# JadePlus_v0_3_1_schematics_PG2_PMS.net
KiCad netlist of a schematic drawn in Altium Designer
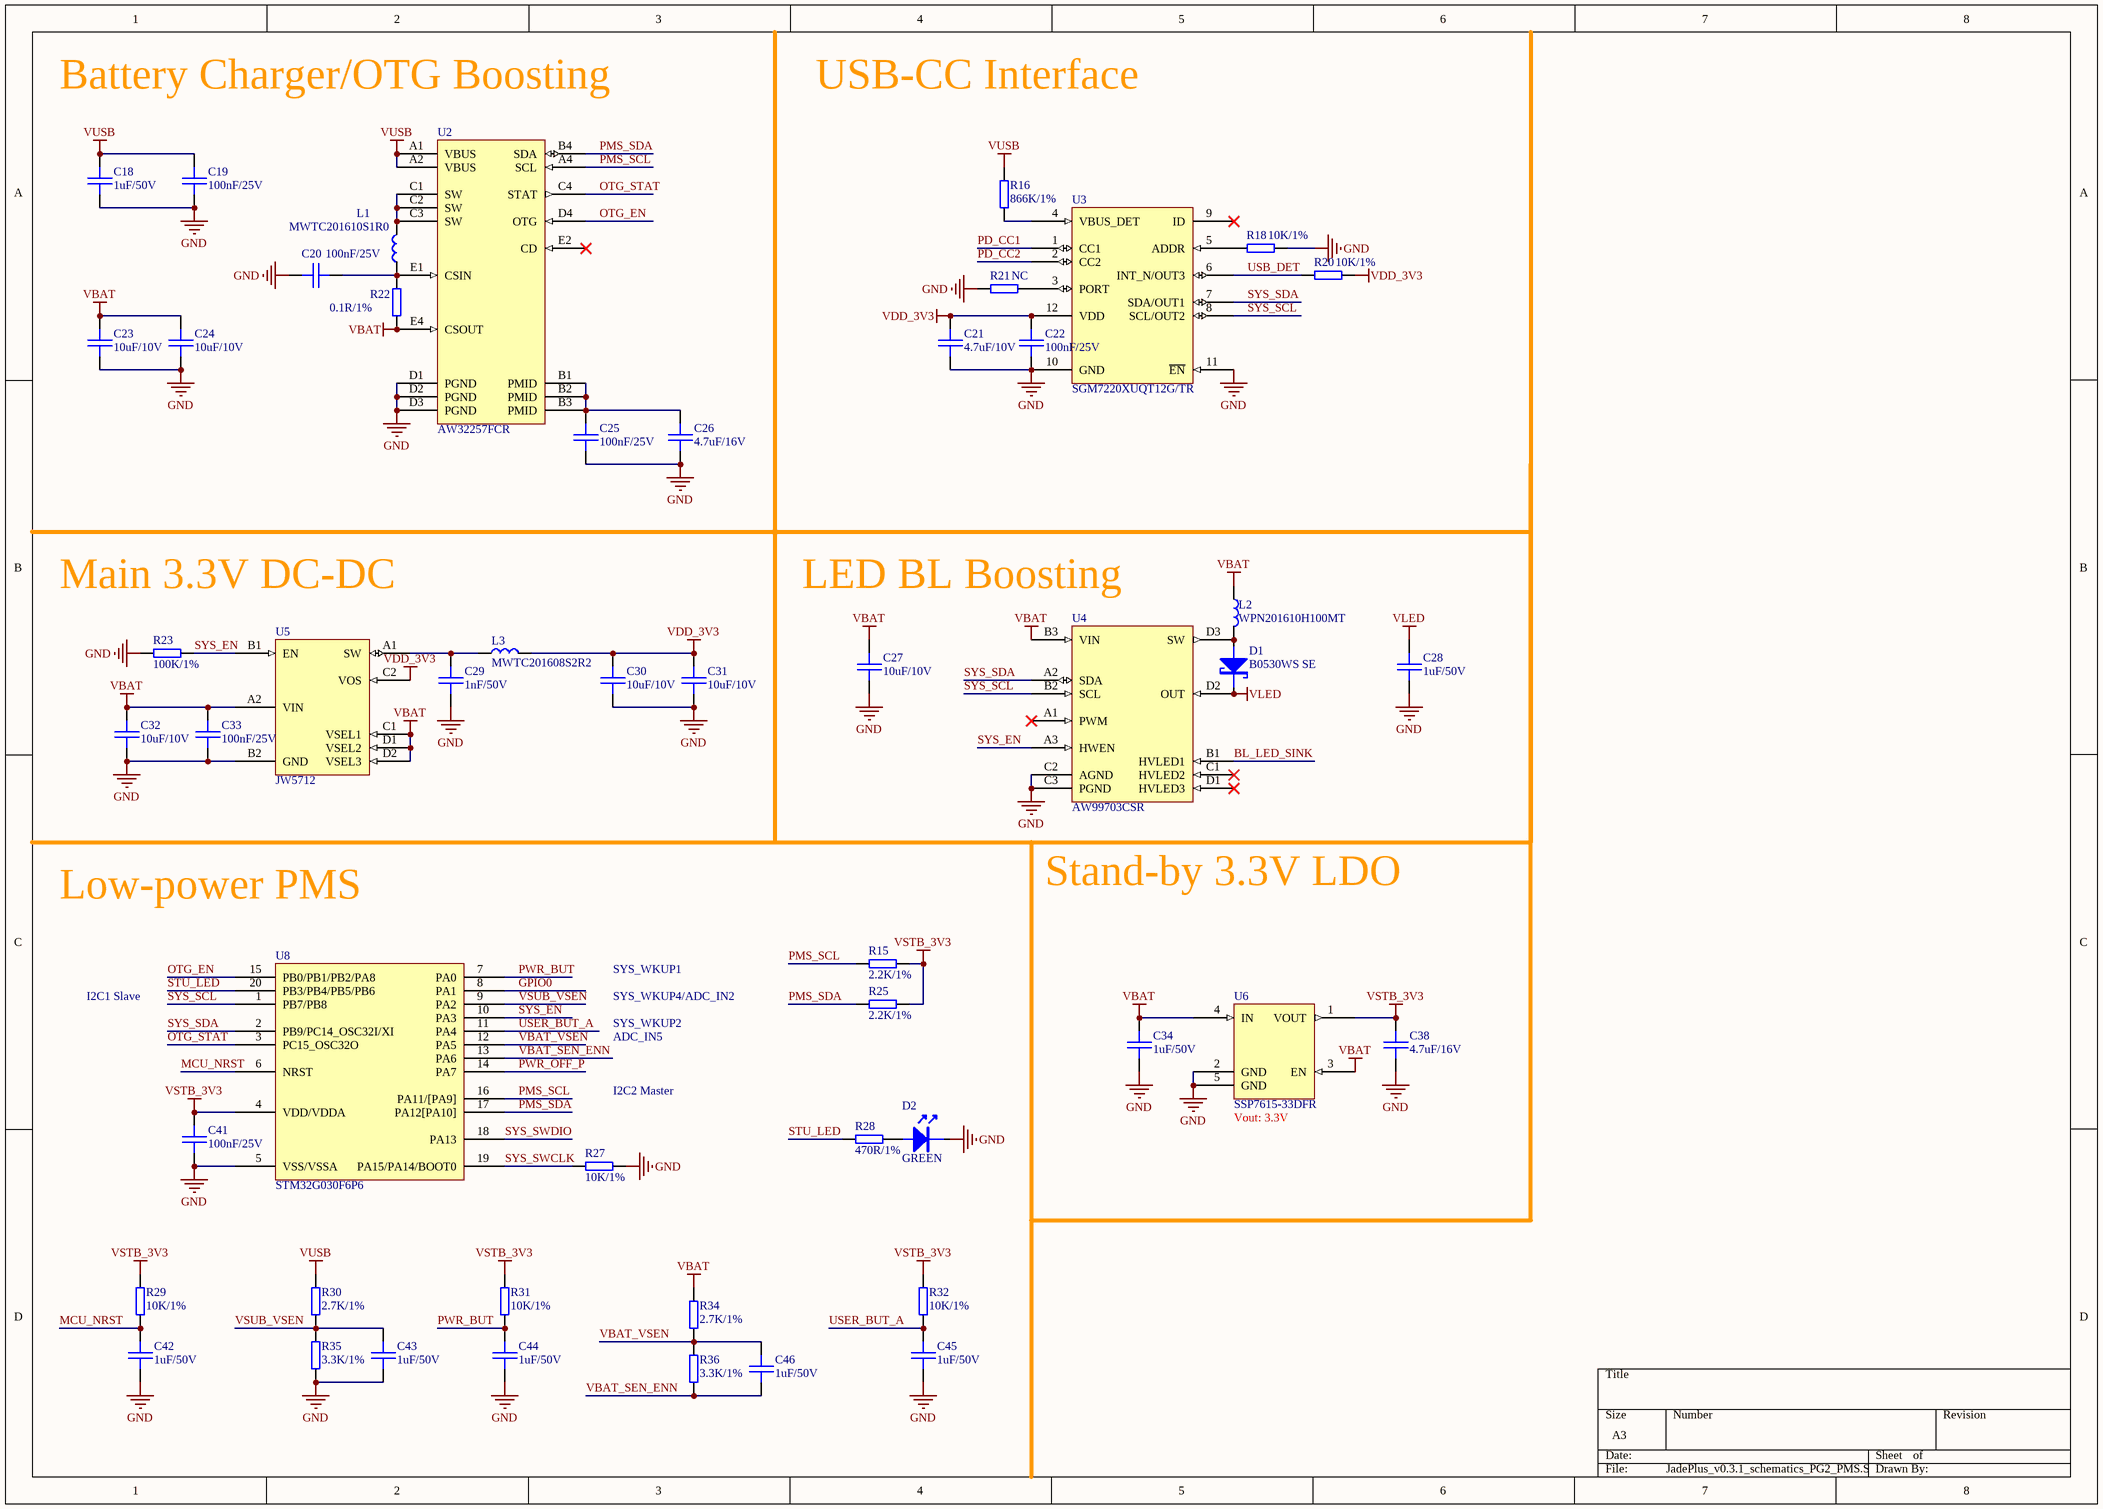
[diagram p0: JadePlus_v0.3.1_schematics_PG2_PMS.SchDoc]

(export (version "E")
  (design (tool "Eeschema 10.0.6"))
  (components
    (comp (ref "C18")
      (value "1uF/50V")
      (footprint "HD-Components:C0402-L-HD")
      (description "Surface mount capacitor 0402")
      (libsource (lib "Vowstar_Basic_Device") (part "SMT_C_0402"))
    )
    (comp (ref "C19")
      (value "100nF/25V")
      (footprint "C0201-HD")
      (description "Surface mount capacitor 0402")
      (libsource (lib "Vowstar_Basic_Device") (part "SMT_C_0402"))
    )
    (comp (ref "C20")
      (value "100nF/25V")
      (footprint "HD-Components:C0402-HD")
      (description "Surface mount capacitor 0402")
      (libsource (lib "Vowstar_Basic_Device") (part "SMT_C_0402"))
    )
    (comp (ref "C21")
      (value "4.7uF/10V")
      (footprint "C0402-L-HD")
      (description "Surface mount capacitor 0402")
      (libsource (lib "Vowstar_Basic_Device") (part "SMT_C_0402"))
    )
    (comp (ref "C22")
      (value "100nF/25V")
      (footprint "C0201-HD")
      (description "Surface mount capacitor 0402")
      (libsource (lib "Vowstar_Basic_Device") (part "SMT_C_0402"))
    )
    (comp (ref "C23")
      (value "10uF/10V")
      (footprint "HD-Components:C0402-L-HD")
      (description "Surface mount capacitor 0402")
      (libsource (lib "Vowstar_Basic_Device") (part "SMT_C_0402"))
    )
    (comp (ref "C24")
      (value "10uF/10V")
      (footprint "HD-Components:C0402-L-HD")
      (description "Surface mount capacitor 0402")
      (libsource (lib "Vowstar_Basic_Device") (part "SMT_C_0402"))
    )
    (comp (ref "C25")
      (value "100nF/25V")
      (footprint "C0201-HD")
      (description "Surface mount capacitor 0402")
      (libsource (lib "Vowstar_Basic_Device") (part "SMT_C_0402"))
    )
    (comp (ref "C26")
      (value "4.7uF/16V")
      (footprint "HD-Components:C0402-L-HD")
      (description "Surface mount capacitor 0402")
      (libsource (lib "Vowstar_Basic_Device") (part "SMT_C_0402"))
    )
    (comp (ref "C27")
      (value "10uF/10V")
      (footprint "HD-Components:C0402-L-HD")
      (description "Surface mount capacitor 0402")
      (libsource (lib "Vowstar_Basic_Device") (part "SMT_C_0402"))
    )
    (comp (ref "C28")
      (value "1uF/50V")
      (footprint "HD-Components:C0402-L-HD")
      (description "Surface mount capacitor 0402")
      (libsource (lib "Vowstar_Basic_Device") (part "SMT_C_0402"))
    )
    (comp (ref "C29")
      (value "1nF/50V")
      (footprint "C0201-HD")
      (description "Surface mount capacitor 0402")
      (libsource (lib "Vowstar_Basic_Device") (part "SMT_C_0402"))
    )
    (comp (ref "C30")
      (value "10uF/10V")
      (footprint "HD-Components:C0402-L-HD")
      (description "Surface mount capacitor 0402")
      (libsource (lib "Vowstar_Basic_Device") (part "SMT_C_0402"))
    )
    (comp (ref "C31")
      (value "10uF/10V")
      (footprint "HD-Components:C0402-L-HD")
      (description "Surface mount capacitor 0402")
      (libsource (lib "Vowstar_Basic_Device") (part "SMT_C_0402"))
    )
    (comp (ref "C32")
      (value "10uF/10V")
      (footprint "HD-Components:C0402-L-HD")
      (description "Surface mount capacitor 0402")
      (libsource (lib "Vowstar_Basic_Device") (part "SMT_C_0402"))
    )
    (comp (ref "C33")
      (value "100nF/25V")
      (footprint "C0201-HD")
      (description "Surface mount capacitor 0402")
      (libsource (lib "Vowstar_Basic_Device") (part "SMT_C_0402"))
    )
    (comp (ref "C34")
      (value "1uF/50V")
      (footprint "HD-Components:C0402-L-HD")
      (description "Surface mount capacitor 0402")
      (libsource (lib "Vowstar_Basic_Device") (part "SMT_C_0402"))
    )
    (comp (ref "C38")
      (value "4.7uF/16V")
      (footprint "HD-Components:C0402-L-HD")
      (description "Surface mount capacitor 0402")
      (libsource (lib "Vowstar_Basic_Device") (part "SMT_C_0402"))
    )
    (comp (ref "C41")
      (value "100nF/25V")
      (footprint "C0201-HD")
      (description "Surface mount capacitor 0402")
      (libsource (lib "Vowstar_Basic_Device") (part "SMT_C_0402"))
    )
    (comp (ref "C42")
      (value "1uF/50V")
      (footprint "HD-Components:C0402-L-HD")
      (description "Surface mount capacitor 0402")
      (libsource (lib "Vowstar_Basic_Device") (part "SMT_C_0402"))
    )
    (comp (ref "C43")
      (value "1uF/50V")
      (footprint "HD-Components:C0402-L-HD")
      (description "Surface mount capacitor 0402")
      (libsource (lib "Vowstar_Basic_Device") (part "SMT_C_0402"))
    )
    (comp (ref "C44")
      (value "1uF/50V")
      (footprint "HD-Components:C0402-L-HD")
      (description "Surface mount capacitor 0402")
      (libsource (lib "Vowstar_Basic_Device") (part "SMT_C_0402"))
    )
    (comp (ref "C45")
      (value "1uF/50V")
      (footprint "HD-Components:C0402-L-HD")
      (description "Surface mount capacitor 0402")
      (libsource (lib "Vowstar_Basic_Device") (part "SMT_C_0402"))
    )
    (comp (ref "C46")
      (value "1uF/50V")
      (footprint "HD-Components:C0402-L-HD")
      (description "Surface mount capacitor 0402")
      (libsource (lib "Vowstar_Basic_Device") (part "SMT_C_0402"))
    )
    (comp (ref "D1")
      (value "B0530WS SE")
      (footprint "SMT_DIODE_SOD_323")
      (description "Surface mount schottky diode SOD-323(0805) Package\r\nC22626")
      (libsource (lib "Vowstar_Basic_Device") (part "SMT_DIODE_SCHOTTKY_SOD_323"))
    )
    (comp (ref "D2")
      (value "GREEN")
      (footprint "SMT_LED_0603")
      (description "Surface mount LED 0603")
      (libsource (lib "Vowstar_Basic_Device") (part "SMT_LED_0603"))
    )
    (comp (ref "L1")
      (value "MWTC201610S1R0")
      (footprint "MWTC201610-HD")
      (description "Surface mount inductor 0805")
      (libsource (lib "") (part "SMT_L_0805_1"))
    )
    (comp (ref "L2")
      (value "WPN201610H100MT")
      (footprint "MWTC201610-HD")
      (description "Surface mount inductor 0805")
      (libsource (lib "Vowstar_Basic_Device") (part "SMT_L_0805"))
    )
    (comp (ref "L3")
      (value "MWTC201608S2R2")
      (footprint "MWTC201610-HD")
      (description "Surface mount inductor 0805")
      (libsource (lib "") (part "SMT_L_0805_1"))
    )
    (comp (ref "R15")
      (value "2.2K/1%")
      (footprint "R0402-HD")
      (description "Surface mount resistor 0402")
      (libsource (lib "Vowstar_Basic_Device") (part "SMT_R_0402"))
    )
    (comp (ref "R16")
      (value "866K/1%")
      (footprint "R0402-HD")
      (description "Surface mount resistor 0402")
      (libsource (lib "Vowstar_Basic_Device") (part "SMT_R_0402"))
    )
    (comp (ref "R18")
      (value "10K/1%")
      (footprint "R0402-HD")
      (description "Surface mount resistor 0402")
      (libsource (lib "Vowstar_Basic_Device") (part "SMT_R_0402"))
    )
    (comp (ref "R20")
      (value "10K/1%")
      (footprint "R0402-HD")
      (description "Surface mount resistor 0402")
      (libsource (lib "Vowstar_Basic_Device") (part "SMT_R_0402"))
    )
    (comp (ref "R21")
      (value "NC")
      (footprint "R0402-HD")
      (description "Surface mount resistor 0402")
      (libsource (lib "Vowstar_Basic_Device") (part "SMT_R_0402"))
    )
    (comp (ref "R22")
      (value "0.1R/1%")
      (footprint "R0603-HD")
      (description "Surface mount resistor 0603")
      (libsource (lib "Vowstar_Basic_Device") (part "SMT_R_0603"))
    )
    (comp (ref "R23")
      (value "100K/1%")
      (footprint "R0402-HD")
      (description "Surface mount resistor 0402")
      (libsource (lib "Vowstar_Basic_Device") (part "SMT_R_0402"))
    )
    (comp (ref "R25")
      (value "2.2K/1%")
      (footprint "R0402-HD")
      (description "Surface mount resistor 0402")
      (libsource (lib "Vowstar_Basic_Device") (part "SMT_R_0402"))
    )
    (comp (ref "R27")
      (value "10K/1%")
      (footprint "R0402-HD")
      (description "Surface mount resistor 0402")
      (libsource (lib "Vowstar_Basic_Device") (part "SMT_R_0402"))
    )
    (comp (ref "R28")
      (value "470R/1%")
      (footprint "R0402-HD")
      (description "Surface mount resistor 0402")
      (libsource (lib "Vowstar_Basic_Device") (part "SMT_R_0402"))
    )
    (comp (ref "R29")
      (value "10K/1%")
      (footprint "R0402-HD")
      (description "Surface mount resistor 0402")
      (libsource (lib "Vowstar_Basic_Device") (part "SMT_R_0402"))
    )
    (comp (ref "R30")
      (value "2.7K/1%")
      (footprint "R0402-HD")
      (description "Surface mount resistor 0402")
      (libsource (lib "Vowstar_Basic_Device") (part "SMT_R_0402"))
    )
    (comp (ref "R31")
      (value "10K/1%")
      (footprint "R0402-HD")
      (description "Surface mount resistor 0402")
      (libsource (lib "Vowstar_Basic_Device") (part "SMT_R_0402"))
    )
    (comp (ref "R32")
      (value "10K/1%")
      (footprint "R0402-HD")
      (description "Surface mount resistor 0402")
      (libsource (lib "Vowstar_Basic_Device") (part "SMT_R_0402"))
    )
    (comp (ref "R34")
      (value "2.7K/1%")
      (footprint "R0402-HD")
      (description "Surface mount resistor 0402")
      (libsource (lib "Vowstar_Basic_Device") (part "SMT_R_0402"))
    )
    (comp (ref "R35")
      (value "3.3K/1%")
      (footprint "R0402-HD")
      (description "Surface mount resistor 0402")
      (libsource (lib "Vowstar_Basic_Device") (part "SMT_R_0402"))
    )
    (comp (ref "R36")
      (value "3.3K/1%")
      (footprint "R0402-HD")
      (description "Surface mount resistor 0402")
      (libsource (lib "Vowstar_Basic_Device") (part "SMT_R_0402"))
    )
    (comp (ref "U2")
      (value "AW32257FCR")
      (footprint "BGA20C40P4X5_200X200X60")
      (libsource (lib "GENERAL-IC") (part "AW32257"))
    )
    (comp (ref "U3")
      (value "SGM7220XUQT12G/TR")
      (footprint "QFN40P160X160X60-12L")
      (description "SGM7220XUQT12G/TR\r\nTUSB320\r\nHUSB320_BA000-QN12R")
      (libsource (lib "GENERAL-IC") (part "SGM7220"))
    )
    (comp (ref "U4")
      (value "AW99703CSR")
      (footprint "BGA12C40P3X4_124X164X64")
      (libsource (lib "GENERAL-IC") (part "AW99703"))
    )
    (comp (ref "U5")
      (value "JW5712")
      (footprint "BGA8C40P2X4_86X156X60")
      (libsource (lib "GENERAL-IC") (part "JW5712"))
    )
    (comp (ref "U6")
      (value "SSP7615-33DFR")
      (footprint "X2SON4")
      (description "300mA HIGH PSRR LOW NOISE LDO WITH ENABLE")
      (libsource (lib "GENERAL-IC") (part "AP7343"))
    )
    (comp (ref "U8")
      (value "STM32G030F6P6")
      (footprint "TSOP-20-HD")
      (libsource (lib "GENERAL-IC") (part "STM32G030F6P6"))
    )
  )
  (nets
    (net (code "1") (name "/BL_LED_SINK") (class "Default")
      (node (ref "U4") (pin "B1") (pinfunction "HVLED1_B1") (pintype "input"))
    )
    (net (code "2") (name "/GPIO0") (class "Default")
      (node (ref "U8") (pin "8") (pinfunction "PA1_8") (pintype "passive"))
    )
    (net (code "3") (name "/MCU_NRST") (class "Default")
      (node (ref "C42") (pin "2") (pinfunction "2_2") (pintype "passive"))
      (node (ref "R29") (pin "2") (pinfunction "2_2") (pintype "passive"))
      (node (ref "U8") (pin "6") (pinfunction "NRST_6") (pintype "passive"))
    )
    (net (code "4") (name "/OTG_EN") (class "Default")
      (node (ref "U2") (pin "D4") (pinfunction "OTG_D4") (pintype "input"))
      (node (ref "U8") (pin "15") (pinfunction "PB0/PB1/PB2/PA8_15") (pintype "passive"))
    )
    (net (code "5") (name "/OTG_STAT") (class "Default")
      (node (ref "U2") (pin "C4") (pinfunction "STAT_C4") (pintype "output"))
      (node (ref "U8") (pin "3") (pinfunction "PC15_OSC32O_3") (pintype "passive"))
    )
    (net (code "6") (name "/PD_CC1") (class "Default")
      (node (ref "U3") (pin "1") (pinfunction "CC1_1") (pintype "bidirectional"))
    )
    (net (code "7") (name "/PD_CC2") (class "Default")
      (node (ref "U3") (pin "2") (pinfunction "CC2_2") (pintype "bidirectional"))
    )
    (net (code "8") (name "/PMS_SCL") (class "Default")
      (node (ref "R15") (pin "1") (pinfunction "1_1") (pintype "passive"))
      (node (ref "U2") (pin "A4") (pinfunction "SCL_A4") (pintype "input"))
      (node (ref "U8") (pin "16") (pinfunction "PA11/[PA9]_16") (pintype "passive"))
    )
    (net (code "9") (name "/PMS_SDA") (class "Default")
      (node (ref "R25") (pin "1") (pinfunction "1_1") (pintype "passive"))
      (node (ref "U2") (pin "B4") (pinfunction "SDA_B4") (pintype "bidirectional"))
      (node (ref "U8") (pin "17") (pinfunction "PA12[PA10]_17") (pintype "passive"))
    )
    (net (code "10") (name "/PWR_BUT") (class "Default")
      (node (ref "C44") (pin "2") (pinfunction "2_2") (pintype "passive"))
      (node (ref "R31") (pin "2") (pinfunction "2_2") (pintype "passive"))
      (node (ref "U8") (pin "7") (pinfunction "PA0_7") (pintype "passive"))
    )
    (net (code "11") (name "/PWR_OFF_P") (class "Default")
      (node (ref "U8") (pin "14") (pinfunction "PA7_14") (pintype "passive"))
    )
    (net (code "12") (name "/STU_LED") (class "Default")
      (node (ref "R28") (pin "2") (pinfunction "2_2") (pintype "passive"))
      (node (ref "U8") (pin "20") (pinfunction "PB3/PB4/PB5/PB6_20") (pintype "passive"))
    )
    (net (code "13") (name "/SYS_EN") (class "Default")
      (node (ref "R23") (pin "2") (pinfunction "2_2") (pintype "passive"))
      (node (ref "U4") (pin "A3") (pinfunction "HWEN_A3") (pintype "input"))
      (node (ref "U5") (pin "B1") (pinfunction "EN_B1") (pintype "input"))
      (node (ref "U8") (pin "10") (pinfunction "PA3_10") (pintype "passive"))
    )
    (net (code "14") (name "/SYS_SCL") (class "Default")
      (node (ref "U3") (pin "8") (pinfunction "SCL/OUT2_8") (pintype "bidirectional"))
      (node (ref "U4") (pin "B2") (pinfunction "SCL_B2") (pintype "input"))
      (node (ref "U8") (pin "1") (pinfunction "PB7/PB8_1") (pintype "passive"))
    )
    (net (code "15") (name "/SYS_SDA") (class "Default")
      (node (ref "U3") (pin "7") (pinfunction "SDA/OUT1_7") (pintype "bidirectional"))
      (node (ref "U4") (pin "A2") (pinfunction "SDA_A2") (pintype "bidirectional"))
      (node (ref "U8") (pin "2") (pinfunction "PB9/PC14_OSC32I/XI_2") (pintype "passive"))
    )
    (net (code "16") (name "/SYS_SWCLK") (class "Default")
      (node (ref "R27") (pin "2") (pinfunction "2_2") (pintype "passive"))
      (node (ref "U8") (pin "19") (pinfunction "PA15/PA14/BOOT0_19") (pintype "passive"))
    )
    (net (code "17") (name "/SYS_SWDIO") (class "Default")
      (node (ref "U8") (pin "18") (pinfunction "PA13_18") (pintype "passive"))
    )
    (net (code "18") (name "/USB_DET") (class "Default")
      (node (ref "R20") (pin "1") (pinfunction "1_1") (pintype "passive"))
      (node (ref "U3") (pin "6") (pinfunction "INT_N/OUT3_6") (pintype "bidirectional"))
    )
    (net (code "19") (name "/USER_BUT_A") (class "Default")
      (node (ref "C45") (pin "2") (pinfunction "2_2") (pintype "passive"))
      (node (ref "R32") (pin "2") (pinfunction "2_2") (pintype "passive"))
      (node (ref "U8") (pin "11") (pinfunction "PA4_11") (pintype "passive"))
    )
    (net (code "20") (name "/VBAT_SEN_ENN") (class "Default")
      (node (ref "C46") (pin "1") (pinfunction "1_1") (pintype "passive"))
      (node (ref "R36") (pin "2") (pinfunction "2_2") (pintype "passive"))
      (node (ref "U8") (pin "13") (pinfunction "PA6_13") (pintype "passive"))
    )
    (net (code "21") (name "/VBAT_VSEN") (class "Default")
      (node (ref "C46") (pin "2") (pinfunction "2_2") (pintype "passive"))
      (node (ref "R34") (pin "2") (pinfunction "2_2") (pintype "passive"))
      (node (ref "R36") (pin "1") (pinfunction "1_1") (pintype "passive"))
      (node (ref "U8") (pin "12") (pinfunction "PA5_12") (pintype "passive"))
    )
    (net (code "22") (name "/VSUB_VSEN") (class "Default")
      (node (ref "C43") (pin "2") (pinfunction "2_2") (pintype "passive"))
      (node (ref "R30") (pin "2") (pinfunction "2_2") (pintype "passive"))
      (node (ref "R35") (pin "1") (pinfunction "1_1") (pintype "passive"))
      (node (ref "U8") (pin "9") (pinfunction "PA2_9") (pintype "passive"))
    )
    (net (code "23") (name "GND") (class "Default")
      (node (ref "C18") (pin "1") (pinfunction "1_1") (pintype "passive"))
      (node (ref "C19") (pin "1") (pinfunction "1_1") (pintype "passive"))
      (node (ref "C20") (pin "2") (pinfunction "2_2") (pintype "passive"))
      (node (ref "C21") (pin "1") (pinfunction "1_1") (pintype "passive"))
      (node (ref "C22") (pin "1") (pinfunction "1_1") (pintype "passive"))
      (node (ref "C23") (pin "1") (pinfunction "1_1") (pintype "passive"))
      (node (ref "C24") (pin "1") (pinfunction "1_1") (pintype "passive"))
      (node (ref "C25") (pin "1") (pinfunction "1_1") (pintype "passive"))
      (node (ref "C26") (pin "1") (pinfunction "1_1") (pintype "passive"))
      (node (ref "C27") (pin "1") (pinfunction "1_1") (pintype "passive"))
      (node (ref "C28") (pin "1") (pinfunction "1_1") (pintype "passive"))
      (node (ref "C29") (pin "1") (pinfunction "1_1") (pintype "passive"))
      (node (ref "C30") (pin "1") (pinfunction "1_1") (pintype "passive"))
      (node (ref "C31") (pin "1") (pinfunction "1_1") (pintype "passive"))
      (node (ref "C32") (pin "1") (pinfunction "1_1") (pintype "passive"))
      (node (ref "C33") (pin "1") (pinfunction "1_1") (pintype "passive"))
      (node (ref "C34") (pin "1") (pinfunction "1_1") (pintype "passive"))
      (node (ref "C38") (pin "1") (pinfunction "1_1") (pintype "passive"))
      (node (ref "C41") (pin "1") (pinfunction "1_1") (pintype "passive"))
      (node (ref "C42") (pin "1") (pinfunction "1_1") (pintype "passive"))
      (node (ref "C43") (pin "1") (pinfunction "1_1") (pintype "passive"))
      (node (ref "C44") (pin "1") (pinfunction "1_1") (pintype "passive"))
      (node (ref "C45") (pin "1") (pinfunction "1_1") (pintype "passive"))
      (node (ref "D2") (pin "2") (pinfunction "K_2") (pintype "passive"))
      (node (ref "R18") (pin "2") (pinfunction "2_2") (pintype "passive"))
      (node (ref "R21") (pin "1") (pinfunction "1_1") (pintype "passive"))
      (node (ref "R23") (pin "1") (pinfunction "1_1") (pintype "passive"))
      (node (ref "R27") (pin "1") (pinfunction "1_1") (pintype "passive"))
      (node (ref "R35") (pin "2") (pinfunction "2_2") (pintype "passive"))
      (node (ref "U2") (pin "D1") (pinfunction "PGND_D1") (pintype "power_in"))
      (node (ref "U2") (pin "D2") (pinfunction "PGND_D2") (pintype "power_in"))
      (node (ref "U2") (pin "D3") (pinfunction "PGND_D3") (pintype "power_in"))
      (node (ref "U3") (pin "10") (pinfunction "GND_10") (pintype "power_in"))
      (node (ref "U3") (pin "11") (pinfunction "~{EN}_11") (pintype "input"))
      (node (ref "U4") (pin "C2") (pinfunction "AGND_C2") (pintype "power_in"))
      (node (ref "U4") (pin "C3") (pinfunction "PGND_C3") (pintype "power_in"))
      (node (ref "U5") (pin "B2") (pinfunction "GND_B2") (pintype "power_in"))
      (node (ref "U6") (pin "2") (pinfunction "GND_2") (pintype "power_in"))
      (node (ref "U6") (pin "5") (pinfunction "GND_5") (pintype "power_in"))
      (node (ref "U8") (pin "5") (pinfunction "VSS/VSSA_5") (pintype "passive"))
    )
    (net (code "24") (name "Net-(C25-Pad2)") (class "Default")
      (node (ref "C25") (pin "2") (pinfunction "2_2") (pintype "passive"))
      (node (ref "C26") (pin "2") (pinfunction "2_2") (pintype "passive"))
      (node (ref "U2") (pin "B1") (pinfunction "PMID_B1") (pintype "power_in"))
      (node (ref "U2") (pin "B2") (pinfunction "PMID_B2") (pintype "power_in"))
      (node (ref "U2") (pin "B3") (pinfunction "PMID_B3") (pintype "power_in"))
    )
    (net (code "25") (name "Net-(D1-A)") (class "Default")
      (node (ref "D1") (pin "1") (pinfunction "A_1") (pintype "passive"))
      (node (ref "L2") (pin "2") (pinfunction "2_2") (pintype "passive"))
      (node (ref "U4") (pin "D3") (pinfunction "SW_D3") (pintype "output"))
    )
    (net (code "26") (name "Net-(D2-A)") (class "Default")
      (node (ref "D2") (pin "1") (pinfunction "A_1") (pintype "passive"))
      (node (ref "R28") (pin "1") (pinfunction "1_1") (pintype "passive"))
    )
    (net (code "27") (name "Net-(L1-Pad1)") (class "Default")
      (node (ref "L1") (pin "1") (pinfunction "1_1") (pintype "passive"))
      (node (ref "U2") (pin "C1") (pinfunction "SW_C1") (pintype "power_in"))
      (node (ref "U2") (pin "C2") (pinfunction "SW_C2") (pintype "power_in"))
      (node (ref "U2") (pin "C3") (pinfunction "SW_C3") (pintype "power_in"))
    )
    (net (code "28") (name "Net-(U2-CSIN)") (class "Default")
      (node (ref "C20") (pin "1") (pinfunction "1_1") (pintype "passive"))
      (node (ref "L1") (pin "2") (pinfunction "2_2") (pintype "passive"))
      (node (ref "R22") (pin "2") (pinfunction "2_2") (pintype "passive"))
      (node (ref "U2") (pin "E1") (pinfunction "CSIN_E1") (pintype "input"))
    )
    (net (code "29") (name "Net-(U3-ADDR)") (class "Default")
      (node (ref "R18") (pin "1") (pinfunction "1_1") (pintype "passive"))
      (node (ref "U3") (pin "5") (pinfunction "ADDR_5") (pintype "input"))
    )
    (net (code "30") (name "Net-(U3-PORT)") (class "Default")
      (node (ref "R21") (pin "2") (pinfunction "2_2") (pintype "passive"))
      (node (ref "U3") (pin "3") (pinfunction "PORT_3") (pintype "bidirectional"))
    )
    (net (code "31") (name "Net-(U3-VBUS_DET)") (class "Default")
      (node (ref "R16") (pin "2") (pinfunction "2_2") (pintype "passive"))
      (node (ref "U3") (pin "4") (pinfunction "VBUS_DET_4") (pintype "input"))
    )
    (net (code "32") (name "Net-(U5-SW)") (class "Default")
      (node (ref "C29") (pin "2") (pinfunction "2_2") (pintype "passive"))
      (node (ref "L3") (pin "2") (pinfunction "2_2") (pintype "passive"))
      (node (ref "U5") (pin "A1") (pinfunction "SW_A1") (pintype "bidirectional"))
    )
    (net (code "33") (name "VBAT") (class "Default")
      (node (ref "C23") (pin "2") (pinfunction "2_2") (pintype "passive"))
      (node (ref "C24") (pin "2") (pinfunction "2_2") (pintype "passive"))
      (node (ref "C27") (pin "2") (pinfunction "2_2") (pintype "passive"))
      (node (ref "C32") (pin "2") (pinfunction "2_2") (pintype "passive"))
      (node (ref "C33") (pin "2") (pinfunction "2_2") (pintype "passive"))
      (node (ref "C34") (pin "2") (pinfunction "2_2") (pintype "passive"))
      (node (ref "L2") (pin "1") (pinfunction "1_1") (pintype "passive"))
      (node (ref "R22") (pin "1") (pinfunction "1_1") (pintype "passive"))
      (node (ref "R34") (pin "1") (pinfunction "1_1") (pintype "passive"))
      (node (ref "U2") (pin "E4") (pinfunction "CSOUT_E4") (pintype "input"))
      (node (ref "U4") (pin "B3") (pinfunction "VIN_B3") (pintype "input"))
      (node (ref "U5") (pin "A2") (pinfunction "VIN_A2") (pintype "power_in"))
      (node (ref "U5") (pin "C1") (pinfunction "VSEL1_C1") (pintype "input"))
      (node (ref "U5") (pin "D1") (pinfunction "VSEL2_D1") (pintype "input"))
      (node (ref "U5") (pin "D2") (pinfunction "VSEL3_D2") (pintype "input"))
      (node (ref "U6") (pin "3") (pinfunction "EN_3") (pintype "input"))
      (node (ref "U6") (pin "4") (pinfunction "IN_4") (pintype "input"))
    )
    (net (code "34") (name "VDD_3V3") (class "Default")
      (node (ref "C21") (pin "2") (pinfunction "2_2") (pintype "passive"))
      (node (ref "C22") (pin "2") (pinfunction "2_2") (pintype "passive"))
      (node (ref "C30") (pin "2") (pinfunction "2_2") (pintype "passive"))
      (node (ref "C31") (pin "2") (pinfunction "2_2") (pintype "passive"))
      (node (ref "L3") (pin "1") (pinfunction "1_1") (pintype "passive"))
      (node (ref "R20") (pin "2") (pinfunction "2_2") (pintype "passive"))
      (node (ref "U3") (pin "12") (pinfunction "VDD_12") (pintype "power_in"))
      (node (ref "U5") (pin "C2") (pinfunction "VOS_C2") (pintype "input"))
    )
    (net (code "35") (name "VLED") (class "Default")
      (node (ref "C28") (pin "2") (pinfunction "2_2") (pintype "passive"))
      (node (ref "D1") (pin "2") (pinfunction "K_2") (pintype "passive"))
      (node (ref "U4") (pin "D2") (pinfunction "OUT_D2") (pintype "input"))
    )
    (net (code "36") (name "VSTB_3V3") (class "Default")
      (node (ref "C38") (pin "2") (pinfunction "2_2") (pintype "passive"))
      (node (ref "C41") (pin "2") (pinfunction "2_2") (pintype "passive"))
      (node (ref "R15") (pin "2") (pinfunction "2_2") (pintype "passive"))
      (node (ref "R25") (pin "2") (pinfunction "2_2") (pintype "passive"))
      (node (ref "R29") (pin "1") (pinfunction "1_1") (pintype "passive"))
      (node (ref "R31") (pin "1") (pinfunction "1_1") (pintype "passive"))
      (node (ref "R32") (pin "1") (pinfunction "1_1") (pintype "passive"))
      (node (ref "U6") (pin "1") (pinfunction "VOUT_1") (pintype "output"))
      (node (ref "U8") (pin "4") (pinfunction "VDD/VDDA_4") (pintype "passive"))
    )
    (net (code "37") (name "VUSB") (class "Default")
      (node (ref "C18") (pin "2") (pinfunction "2_2") (pintype "passive"))
      (node (ref "C19") (pin "2") (pinfunction "2_2") (pintype "passive"))
      (node (ref "R16") (pin "1") (pinfunction "1_1") (pintype "passive"))
      (node (ref "R30") (pin "1") (pinfunction "1_1") (pintype "passive"))
      (node (ref "U2") (pin "A1") (pinfunction "VBUS_A1") (pintype "power_in"))
      (node (ref "U2") (pin "A2") (pinfunction "VBUS_A2") (pintype "power_in"))
    )
    (net (code "38") (name "unconnected-(U2-CD-PadE2)") (class "Default")
      (node (ref "U2") (pin "E2") (pinfunction "CD_E2") (pintype "input+no_connect"))
    )
    (net (code "39") (name "unconnected-(U3-ID-Pad9)") (class "Default")
      (node (ref "U3") (pin "9") (pinfunction "ID_9") (pintype "open_collector+no_connect"))
    )
    (net (code "40") (name "unconnected-(U4-HVLED2-PadC1)") (class "Default")
      (node (ref "U4") (pin "C1") (pinfunction "HVLED2_C1") (pintype "input+no_connect"))
    )
    (net (code "41") (name "unconnected-(U4-HVLED3-PadD1)") (class "Default")
      (node (ref "U4") (pin "D1") (pinfunction "HVLED3_D1") (pintype "input+no_connect"))
    )
    (net (code "42") (name "unconnected-(U4-PWM-PadA1)") (class "Default")
      (node (ref "U4") (pin "A1") (pinfunction "PWM_A1") (pintype "input+no_connect"))
    )
  )
)
